# Bank3.net
KiCad netlist of a schematic drawn in Altium Designer
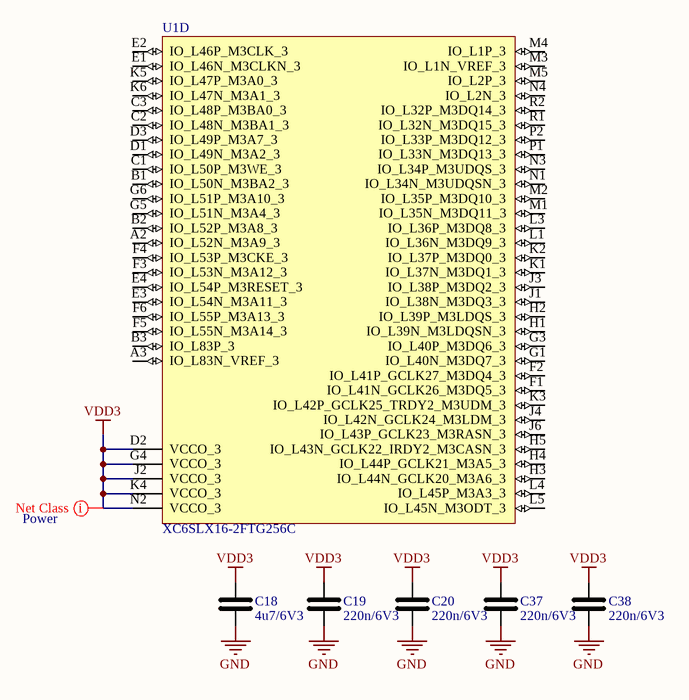
[diagram p0: Bank3.SchDoc]

(export (version "E")
  (design (tool "Eeschema 10.0.6"))
  (components
    (comp (ref "C18") (value "4u7/6V3") (footprint "C0805_N") (libsource (lib "niceCircuits") (part "C")))
    (comp (ref "C19") (value "220n/6V3") (footprint "C0402_N") (libsource (lib "niceCircuits") (part "C")))
    (comp (ref "C20") (value "220n/6V3") (footprint "C0402_N") (libsource (lib "niceCircuits") (part "C")))
    (comp (ref "C37") (value "220n/6V3") (footprint "C0402_N") (libsource (lib "niceCircuits") (part "C")))
    (comp (ref "C38") (value "220n/6V3") (footprint "C0402_N") (libsource (lib "niceCircuits") (part "C")))
    (comp (ref "U1")
      (value "XC6SLX16-2FTG256C")
      (footprint "Xilinx_FT256_L")
      (libsource (lib "niceCircuits") (part "XC6SLX16-2FTG256C"))
    )
  )
  (nets
    (net (code "1") (name "GND") (class "Default")
      (node (ref "C18") (pin "1") (pinfunction "1_1") (pintype "passive"))
      (node (ref "C19") (pin "1") (pinfunction "1_1") (pintype "passive"))
      (node (ref "C20") (pin "1") (pinfunction "1_1") (pintype "passive"))
      (node (ref "C37") (pin "1") (pinfunction "1_1") (pintype "passive"))
      (node (ref "C38") (pin "1") (pinfunction "1_1") (pintype "passive"))
    )
    (net (code "2") (name "VDD3") (class "Default")
      (node (ref "C18") (pin "2") (pinfunction "2_2") (pintype "passive"))
      (node (ref "C19") (pin "2") (pinfunction "2_2") (pintype "passive"))
      (node (ref "C20") (pin "2") (pinfunction "2_2") (pintype "passive"))
      (node (ref "C37") (pin "2") (pinfunction "2_2") (pintype "passive"))
      (node (ref "C38") (pin "2") (pinfunction "2_2") (pintype "passive"))
      (node (ref "U1") (pin "D2") (pinfunction "VCCO_3_D2") (pintype "power_in"))
      (node (ref "U1") (pin "G4") (pinfunction "VCCO_3_G4") (pintype "power_in"))
      (node (ref "U1") (pin "J2") (pinfunction "VCCO_3_J2") (pintype "power_in"))
      (node (ref "U1") (pin "K4") (pinfunction "VCCO_3_K4") (pintype "power_in"))
      (node (ref "U1") (pin "N2") (pinfunction "VCCO_3_N2") (pintype "power_in"))
    )
    (net (code "3") (name "unconnected-(U1D-IO_L1N_VREF_3-PadM3)") (class "Default")
      (node (ref "U1") (pin "M3") (pinfunction "IO_L1N_VREF_3_M3") (pintype "bidirectional"))
    )
    (net (code "4") (name "unconnected-(U1D-IO_L1P_3-PadM4)") (class "Default")
      (node (ref "U1") (pin "M4") (pinfunction "IO_L1P_3_M4") (pintype "bidirectional"))
    )
    (net (code "5") (name "unconnected-(U1D-IO_L2N_3-PadN4)") (class "Default")
      (node (ref "U1") (pin "N4") (pinfunction "IO_L2N_3_N4") (pintype "bidirectional"))
    )
    (net (code "6") (name "unconnected-(U1D-IO_L2P_3-PadM5)") (class "Default")
      (node (ref "U1") (pin "M5") (pinfunction "IO_L2P_3_M5") (pintype "bidirectional"))
    )
    (net (code "7") (name "unconnected-(U1D-IO_L32N_M3DQ15_3-PadR1)") (class "Default")
      (node (ref "U1") (pin "R1") (pinfunction "IO_L32N_M3DQ15_3_R1") (pintype "bidirectional"))
    )
    (net (code "8") (name "unconnected-(U1D-IO_L32P_M3DQ14_3-PadR2)") (class "Default")
      (node (ref "U1") (pin "R2") (pinfunction "IO_L32P_M3DQ14_3_R2") (pintype "bidirectional"))
    )
    (net (code "9") (name "unconnected-(U1D-IO_L33N_M3DQ13_3-PadP1)") (class "Default")
      (node (ref "U1") (pin "P1") (pinfunction "IO_L33N_M3DQ13_3_P1") (pintype "bidirectional"))
    )
    (net (code "10") (name "unconnected-(U1D-IO_L33P_M3DQ12_3-PadP2)") (class "Default")
      (node (ref "U1") (pin "P2") (pinfunction "IO_L33P_M3DQ12_3_P2") (pintype "bidirectional"))
    )
    (net (code "11") (name "unconnected-(U1D-IO_L34N_M3UDQSN_3-PadN1)") (class "Default")
      (node (ref "U1") (pin "N1") (pinfunction "IO_L34N_M3UDQSN_3_N1") (pintype "bidirectional"))
    )
    (net (code "12") (name "unconnected-(U1D-IO_L34P_M3UDQS_3-PadN3)") (class "Default")
      (node (ref "U1") (pin "N3") (pinfunction "IO_L34P_M3UDQS_3_N3") (pintype "bidirectional"))
    )
    (net (code "13") (name "unconnected-(U1D-IO_L35N_M3DQ11_3-PadM1)") (class "Default")
      (node (ref "U1") (pin "M1") (pinfunction "IO_L35N_M3DQ11_3_M1") (pintype "bidirectional"))
    )
    (net (code "14") (name "unconnected-(U1D-IO_L35P_M3DQ10_3-PadM2)") (class "Default")
      (node (ref "U1") (pin "M2") (pinfunction "IO_L35P_M3DQ10_3_M2") (pintype "bidirectional"))
    )
    (net (code "15") (name "unconnected-(U1D-IO_L36N_M3DQ9_3-PadL1)") (class "Default")
      (node (ref "U1") (pin "L1") (pinfunction "IO_L36N_M3DQ9_3_L1") (pintype "bidirectional"))
    )
    (net (code "16") (name "unconnected-(U1D-IO_L36P_M3DQ8_3-PadL3)") (class "Default")
      (node (ref "U1") (pin "L3") (pinfunction "IO_L36P_M3DQ8_3_L3") (pintype "bidirectional"))
    )
    (net (code "17") (name "unconnected-(U1D-IO_L37N_M3DQ1_3-PadK1)") (class "Default")
      (node (ref "U1") (pin "K1") (pinfunction "IO_L37N_M3DQ1_3_K1") (pintype "bidirectional"))
    )
    (net (code "18") (name "unconnected-(U1D-IO_L37P_M3DQ0_3-PadK2)") (class "Default")
      (node (ref "U1") (pin "K2") (pinfunction "IO_L37P_M3DQ0_3_K2") (pintype "bidirectional"))
    )
    (net (code "19") (name "unconnected-(U1D-IO_L38N_M3DQ3_3-PadJ1)") (class "Default")
      (node (ref "U1") (pin "J1") (pinfunction "IO_L38N_M3DQ3_3_J1") (pintype "bidirectional"))
    )
    (net (code "20") (name "unconnected-(U1D-IO_L38P_M3DQ2_3-PadJ3)") (class "Default")
      (node (ref "U1") (pin "J3") (pinfunction "IO_L38P_M3DQ2_3_J3") (pintype "bidirectional"))
    )
    (net (code "21") (name "unconnected-(U1D-IO_L39N_M3LDQSN_3-PadH1)") (class "Default")
      (node (ref "U1") (pin "H1") (pinfunction "IO_L39N_M3LDQSN_3_H1") (pintype "bidirectional"))
    )
    (net (code "22") (name "unconnected-(U1D-IO_L39P_M3LDQS_3-PadH2)") (class "Default")
      (node (ref "U1") (pin "H2") (pinfunction "IO_L39P_M3LDQS_3_H2") (pintype "bidirectional"))
    )
    (net (code "23") (name "unconnected-(U1D-IO_L40N_M3DQ7_3-PadG1)") (class "Default")
      (node (ref "U1") (pin "G1") (pinfunction "IO_L40N_M3DQ7_3_G1") (pintype "bidirectional"))
    )
    (net (code "24") (name "unconnected-(U1D-IO_L40P_M3DQ6_3-PadG3)") (class "Default")
      (node (ref "U1") (pin "G3") (pinfunction "IO_L40P_M3DQ6_3_G3") (pintype "bidirectional"))
    )
    (net (code "25") (name "unconnected-(U1D-IO_L41N_GCLK26_M3DQ5_3-PadF1)") (class "Default")
      (node (ref "U1") (pin "F1") (pinfunction "IO_L41N_GCLK26_M3DQ5_3_F1") (pintype "bidirectional"))
    )
    (net (code "26") (name "unconnected-(U1D-IO_L41P_GCLK27_M3DQ4_3-PadF2)") (class "Default")
      (node (ref "U1") (pin "F2") (pinfunction "IO_L41P_GCLK27_M3DQ4_3_F2") (pintype "bidirectional"))
    )
    (net (code "27") (name "unconnected-(U1D-IO_L42N_GCLK24_M3LDM_3-PadJ4)") (class "Default")
      (node (ref "U1") (pin "J4") (pinfunction "IO_L42N_GCLK24_M3LDM_3_J4") (pintype "bidirectional"))
    )
    (net (code "28") (name "unconnected-(U1D-IO_L42P_GCLK25_TRDY2_M3UDM_3-PadK3)") (class "Default")
      (node (ref "U1") (pin "K3") (pinfunction "IO_L42P_GCLK25_TRDY2_M3UDM_3_K3") (pintype "bidirectional"))
    )
    (net (code "29") (name "unconnected-(U1D-IO_L43N_GCLK22_IRDY2_M3CASN_3-PadH5)") (class "Default")
      (node (ref "U1") (pin "H5") (pinfunction "IO_L43N_GCLK22_IRDY2_M3CASN_3_H5") (pintype "bidirectional"))
    )
    (net (code "30") (name "unconnected-(U1D-IO_L43P_GCLK23_M3RASN_3-PadJ6)") (class "Default")
      (node (ref "U1") (pin "J6") (pinfunction "IO_L43P_GCLK23_M3RASN_3_J6") (pintype "bidirectional"))
    )
    (net (code "31") (name "unconnected-(U1D-IO_L44N_GCLK20_M3A6_3-PadH3)") (class "Default")
      (node (ref "U1") (pin "H3") (pinfunction "IO_L44N_GCLK20_M3A6_3_H3") (pintype "bidirectional"))
    )
    (net (code "32") (name "unconnected-(U1D-IO_L44P_GCLK21_M3A5_3-PadH4)") (class "Default")
      (node (ref "U1") (pin "H4") (pinfunction "IO_L44P_GCLK21_M3A5_3_H4") (pintype "bidirectional"))
    )
    (net (code "33") (name "unconnected-(U1D-IO_L45N_M3ODT_3-PadL5)") (class "Default")
      (node (ref "U1") (pin "L5") (pinfunction "IO_L45N_M3ODT_3_L5") (pintype "bidirectional"))
    )
    (net (code "34") (name "unconnected-(U1D-IO_L45P_M3A3_3-PadL4)") (class "Default")
      (node (ref "U1") (pin "L4") (pinfunction "IO_L45P_M3A3_3_L4") (pintype "bidirectional"))
    )
    (net (code "35") (name "unconnected-(U1D-IO_L46N_M3CLKN_3-PadE1)") (class "Default")
      (node (ref "U1") (pin "E1") (pinfunction "IO_L46N_M3CLKN_3_E1") (pintype "bidirectional"))
    )
    (net (code "36") (name "unconnected-(U1D-IO_L46P_M3CLK_3-PadE2)") (class "Default")
      (node (ref "U1") (pin "E2") (pinfunction "IO_L46P_M3CLK_3_E2") (pintype "bidirectional"))
    )
    (net (code "37") (name "unconnected-(U1D-IO_L47N_M3A1_3-PadK6)") (class "Default")
      (node (ref "U1") (pin "K6") (pinfunction "IO_L47N_M3A1_3_K6") (pintype "bidirectional"))
    )
    (net (code "38") (name "unconnected-(U1D-IO_L47P_M3A0_3-PadK5)") (class "Default")
      (node (ref "U1") (pin "K5") (pinfunction "IO_L47P_M3A0_3_K5") (pintype "bidirectional"))
    )
    (net (code "39") (name "unconnected-(U1D-IO_L48N_M3BA1_3-PadC2)") (class "Default")
      (node (ref "U1") (pin "C2") (pinfunction "IO_L48N_M3BA1_3_C2") (pintype "bidirectional"))
    )
    (net (code "40") (name "unconnected-(U1D-IO_L48P_M3BA0_3-PadC3)") (class "Default")
      (node (ref "U1") (pin "C3") (pinfunction "IO_L48P_M3BA0_3_C3") (pintype "bidirectional"))
    )
    (net (code "41") (name "unconnected-(U1D-IO_L49N_M3A2_3-PadD1)") (class "Default")
      (node (ref "U1") (pin "D1") (pinfunction "IO_L49N_M3A2_3_D1") (pintype "bidirectional"))
    )
    (net (code "42") (name "unconnected-(U1D-IO_L49P_M3A7_3-PadD3)") (class "Default")
      (node (ref "U1") (pin "D3") (pinfunction "IO_L49P_M3A7_3_D3") (pintype "bidirectional"))
    )
    (net (code "43") (name "unconnected-(U1D-IO_L50N_M3BA2_3-PadB1)") (class "Default")
      (node (ref "U1") (pin "B1") (pinfunction "IO_L50N_M3BA2_3_B1") (pintype "bidirectional"))
    )
    (net (code "44") (name "unconnected-(U1D-IO_L50P_M3WE_3-PadC1)") (class "Default")
      (node (ref "U1") (pin "C1") (pinfunction "IO_L50P_M3WE_3_C1") (pintype "bidirectional"))
    )
    (net (code "45") (name "unconnected-(U1D-IO_L51N_M3A4_3-PadG5)") (class "Default")
      (node (ref "U1") (pin "G5") (pinfunction "IO_L51N_M3A4_3_G5") (pintype "bidirectional"))
    )
    (net (code "46") (name "unconnected-(U1D-IO_L51P_M3A10_3-PadG6)") (class "Default")
      (node (ref "U1") (pin "G6") (pinfunction "IO_L51P_M3A10_3_G6") (pintype "bidirectional"))
    )
    (net (code "47") (name "unconnected-(U1D-IO_L52N_M3A9_3-PadA2)") (class "Default")
      (node (ref "U1") (pin "A2") (pinfunction "IO_L52N_M3A9_3_A2") (pintype "bidirectional"))
    )
    (net (code "48") (name "unconnected-(U1D-IO_L52P_M3A8_3-PadB2)") (class "Default")
      (node (ref "U1") (pin "B2") (pinfunction "IO_L52P_M3A8_3_B2") (pintype "bidirectional"))
    )
    (net (code "49") (name "unconnected-(U1D-IO_L53N_M3A12_3-PadF3)") (class "Default")
      (node (ref "U1") (pin "F3") (pinfunction "IO_L53N_M3A12_3_F3") (pintype "bidirectional"))
    )
    (net (code "50") (name "unconnected-(U1D-IO_L53P_M3CKE_3-PadF4)") (class "Default")
      (node (ref "U1") (pin "F4") (pinfunction "IO_L53P_M3CKE_3_F4") (pintype "bidirectional"))
    )
    (net (code "51") (name "unconnected-(U1D-IO_L54N_M3A11_3-PadE3)") (class "Default")
      (node (ref "U1") (pin "E3") (pinfunction "IO_L54N_M3A11_3_E3") (pintype "bidirectional"))
    )
    (net (code "52") (name "unconnected-(U1D-IO_L54P_M3RESET_3-PadE4)") (class "Default")
      (node (ref "U1") (pin "E4") (pinfunction "IO_L54P_M3RESET_3_E4") (pintype "bidirectional"))
    )
    (net (code "53") (name "unconnected-(U1D-IO_L55N_M3A14_3-PadF5)") (class "Default")
      (node (ref "U1") (pin "F5") (pinfunction "IO_L55N_M3A14_3_F5") (pintype "bidirectional"))
    )
    (net (code "54") (name "unconnected-(U1D-IO_L55P_M3A13_3-PadF6)") (class "Default")
      (node (ref "U1") (pin "F6") (pinfunction "IO_L55P_M3A13_3_F6") (pintype "bidirectional"))
    )
    (net (code "55") (name "unconnected-(U1D-IO_L83N_VREF_3-PadA3)") (class "Default")
      (node (ref "U1") (pin "A3") (pinfunction "IO_L83N_VREF_3_A3") (pintype "bidirectional"))
    )
    (net (code "56") (name "unconnected-(U1D-IO_L83P_3-PadB3)") (class "Default")
      (node (ref "U1") (pin "B3") (pinfunction "IO_L83P_3_B3") (pintype "bidirectional"))
    )
  )
)
